# Differential_Mode_Filter.net
KiCad netlist of a schematic drawn in Altium Designer
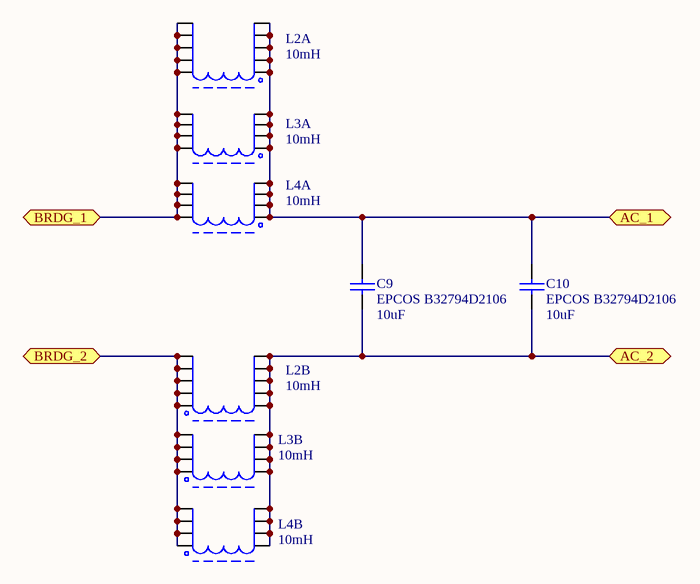
[diagram p0: Differential_Mode_Filter.SchDoc]

(export (version "E")
  (design (tool "Eeschema 10.0.6"))
  (components
    (comp (ref "C9")
      (value "EPCOS B32794D2106")
      (footprint "MKP AC filtering - 10")
      (description "MKP AC Filtering 10uF 630Vdc")
      (fields (field (name "ALTIUM_VALUE") "10uF") (field (name "PUBLISHER") "Altium Limited"))
      (libsource (lib "Capacitor") (part "EPCOS B32794D2106"))
    )
    (comp (ref "C10")
      (value "EPCOS B32794D2106")
      (footprint "MKP AC filtering - 10")
      (description "MKP AC Filtering 10uF 630Vdc")
      (fields (field (name "ALTIUM_VALUE") "10uF") (field (name "PUBLISHER") "Altium Limited"))
      (libsource (lib "Capacitor") (part "EPCOS B32794D2106"))
    )
    (comp (ref "L2")
      (value "10mH")
      (footprint "Core_PM_87/70")
      (description "Coupled Inductors with Ferrite core and Air gap")
      (fields (field (name "Comment") "Coupled Inductors") (field (name "PUBLISHER") "Altium Limited"))
      (libsource (lib "") (part "Inductor 87/70_1"))
    )
    (comp (ref "L3")
      (value "10mH")
      (footprint "Core_PM_74/59")
      (description "Coupled Inductors with Ferrite core and Air gap")
      (fields (field (name "Comment") "Coupled Inductors") (field (name "PUBLISHER") "Altium Limited"))
      (libsource (lib "") (part "Inductor 74/59_1"))
    )
    (comp (ref "L4")
      (value "10mH")
      (footprint "Core_PM_62/49")
      (description "Coupled Inductors with Ferrite core and Air gap")
      (fields (field (name "Comment") "Coupled Inductors") (field (name "PUBLISHER") "Altium Limited"))
      (libsource (lib "") (part "Inductor 62/49_1"))
    )
  )
  (nets
    (net (code "1") (name "/AC_1") (class "Default")
      (node (ref "C10") (pin "2") (pinfunction "2_2") (pintype "passive"))
      (node (ref "C9") (pin "2") (pinfunction "2_2") (pintype "passive"))
      (node (ref "L2") (pin "1") (pinfunction "1_1") (pintype "passive"))
      (node (ref "L2") (pin "2") (pinfunction "2_2") (pintype "passive"))
      (node (ref "L2") (pin "3") (pinfunction "3_3") (pintype "passive"))
      (node (ref "L2") (pin "4") (pinfunction "4_4") (pintype "passive"))
      (node (ref "L2") (pin "5") (pinfunction "5_5") (pintype "passive"))
      (node (ref "L3") (pin "1") (pinfunction "1_1") (pintype "passive"))
      (node (ref "L3") (pin "2") (pinfunction "2_2") (pintype "passive"))
      (node (ref "L3") (pin "3") (pinfunction "3_3") (pintype "passive"))
      (node (ref "L3") (pin "4") (pinfunction "4_4") (pintype "passive"))
      (node (ref "L4") (pin "1") (pinfunction "1_1") (pintype "passive"))
      (node (ref "L4") (pin "2") (pinfunction "2_2") (pintype "passive"))
      (node (ref "L4") (pin "3") (pinfunction "3_3") (pintype "passive"))
      (node (ref "L4") (pin "4") (pinfunction "4_4") (pintype "passive"))
    )
    (net (code "2") (name "/AC_2") (class "Default")
      (node (ref "C10") (pin "1") (pinfunction "1_1") (pintype "passive"))
      (node (ref "C9") (pin "1") (pinfunction "1_1") (pintype "passive"))
      (node (ref "L2") (pin "10") (pinfunction "10_10") (pintype "passive"))
      (node (ref "L2") (pin "6") (pinfunction "6_6") (pintype "passive"))
      (node (ref "L2") (pin "7") (pinfunction "7_7") (pintype "passive"))
      (node (ref "L2") (pin "8") (pinfunction "8_8") (pintype "passive"))
      (node (ref "L2") (pin "9") (pinfunction "9_9") (pintype "passive"))
      (node (ref "L3") (pin "6") (pinfunction "6_6") (pintype "passive"))
      (node (ref "L3") (pin "7") (pinfunction "7_7") (pintype "passive"))
      (node (ref "L3") (pin "8") (pinfunction "8_8") (pintype "passive"))
      (node (ref "L3") (pin "9") (pinfunction "9_9") (pintype "passive"))
      (node (ref "L4") (pin "5") (pinfunction "5_5") (pintype "passive"))
      (node (ref "L4") (pin "6") (pinfunction "6_6") (pintype "passive"))
      (node (ref "L4") (pin "7") (pinfunction "7_7") (pintype "passive"))
      (node (ref "L4") (pin "8") (pinfunction "8_8") (pintype "passive"))
    )
    (net (code "3") (name "/BRDG_1") (class "Default")
      (node (ref "L2") (pin "16") (pinfunction "16_16") (pintype "passive"))
      (node (ref "L2") (pin "17") (pinfunction "17_17") (pintype "passive"))
      (node (ref "L2") (pin "18") (pinfunction "18_18") (pintype "passive"))
      (node (ref "L2") (pin "19") (pinfunction "19_19") (pintype "passive"))
      (node (ref "L2") (pin "20") (pinfunction "20_20") (pintype "passive"))
      (node (ref "L3") (pin "15") (pinfunction "15_15") (pintype "passive"))
      (node (ref "L3") (pin "16") (pinfunction "16_16") (pintype "passive"))
      (node (ref "L3") (pin "17") (pinfunction "17_17") (pintype "passive"))
      (node (ref "L3") (pin "18") (pinfunction "18_18") (pintype "passive"))
      (node (ref "L4") (pin "13") (pinfunction "13_13") (pintype "passive"))
      (node (ref "L4") (pin "14") (pinfunction "14_14") (pintype "passive"))
      (node (ref "L4") (pin "15") (pinfunction "15_15") (pintype "passive"))
      (node (ref "L4") (pin "16") (pinfunction "16_16") (pintype "passive"))
    )
    (net (code "4") (name "/BRDG_2") (class "Default")
      (node (ref "L2") (pin "11") (pinfunction "11_11") (pintype "passive"))
      (node (ref "L2") (pin "12") (pinfunction "12_12") (pintype "passive"))
      (node (ref "L2") (pin "13") (pinfunction "13_13") (pintype "passive"))
      (node (ref "L2") (pin "14") (pinfunction "14_14") (pintype "passive"))
      (node (ref "L2") (pin "15") (pinfunction "15_15") (pintype "passive"))
      (node (ref "L3") (pin "10") (pinfunction "10_10") (pintype "passive"))
      (node (ref "L3") (pin "11") (pinfunction "11_11") (pintype "passive"))
      (node (ref "L3") (pin "12") (pinfunction "12_12") (pintype "passive"))
      (node (ref "L3") (pin "13") (pinfunction "13_13") (pintype "passive"))
      (node (ref "L4") (pin "10") (pinfunction "10_10") (pintype "passive"))
      (node (ref "L4") (pin "11") (pinfunction "11_11") (pintype "passive"))
      (node (ref "L4") (pin "12") (pinfunction "12_12") (pintype "passive"))
      (node (ref "L4") (pin "9") (pinfunction "9_9") (pintype "passive"))
    )
  )
)
